# rpi_shield.net
KiCad netlist of a schematic drawn in EAGLE
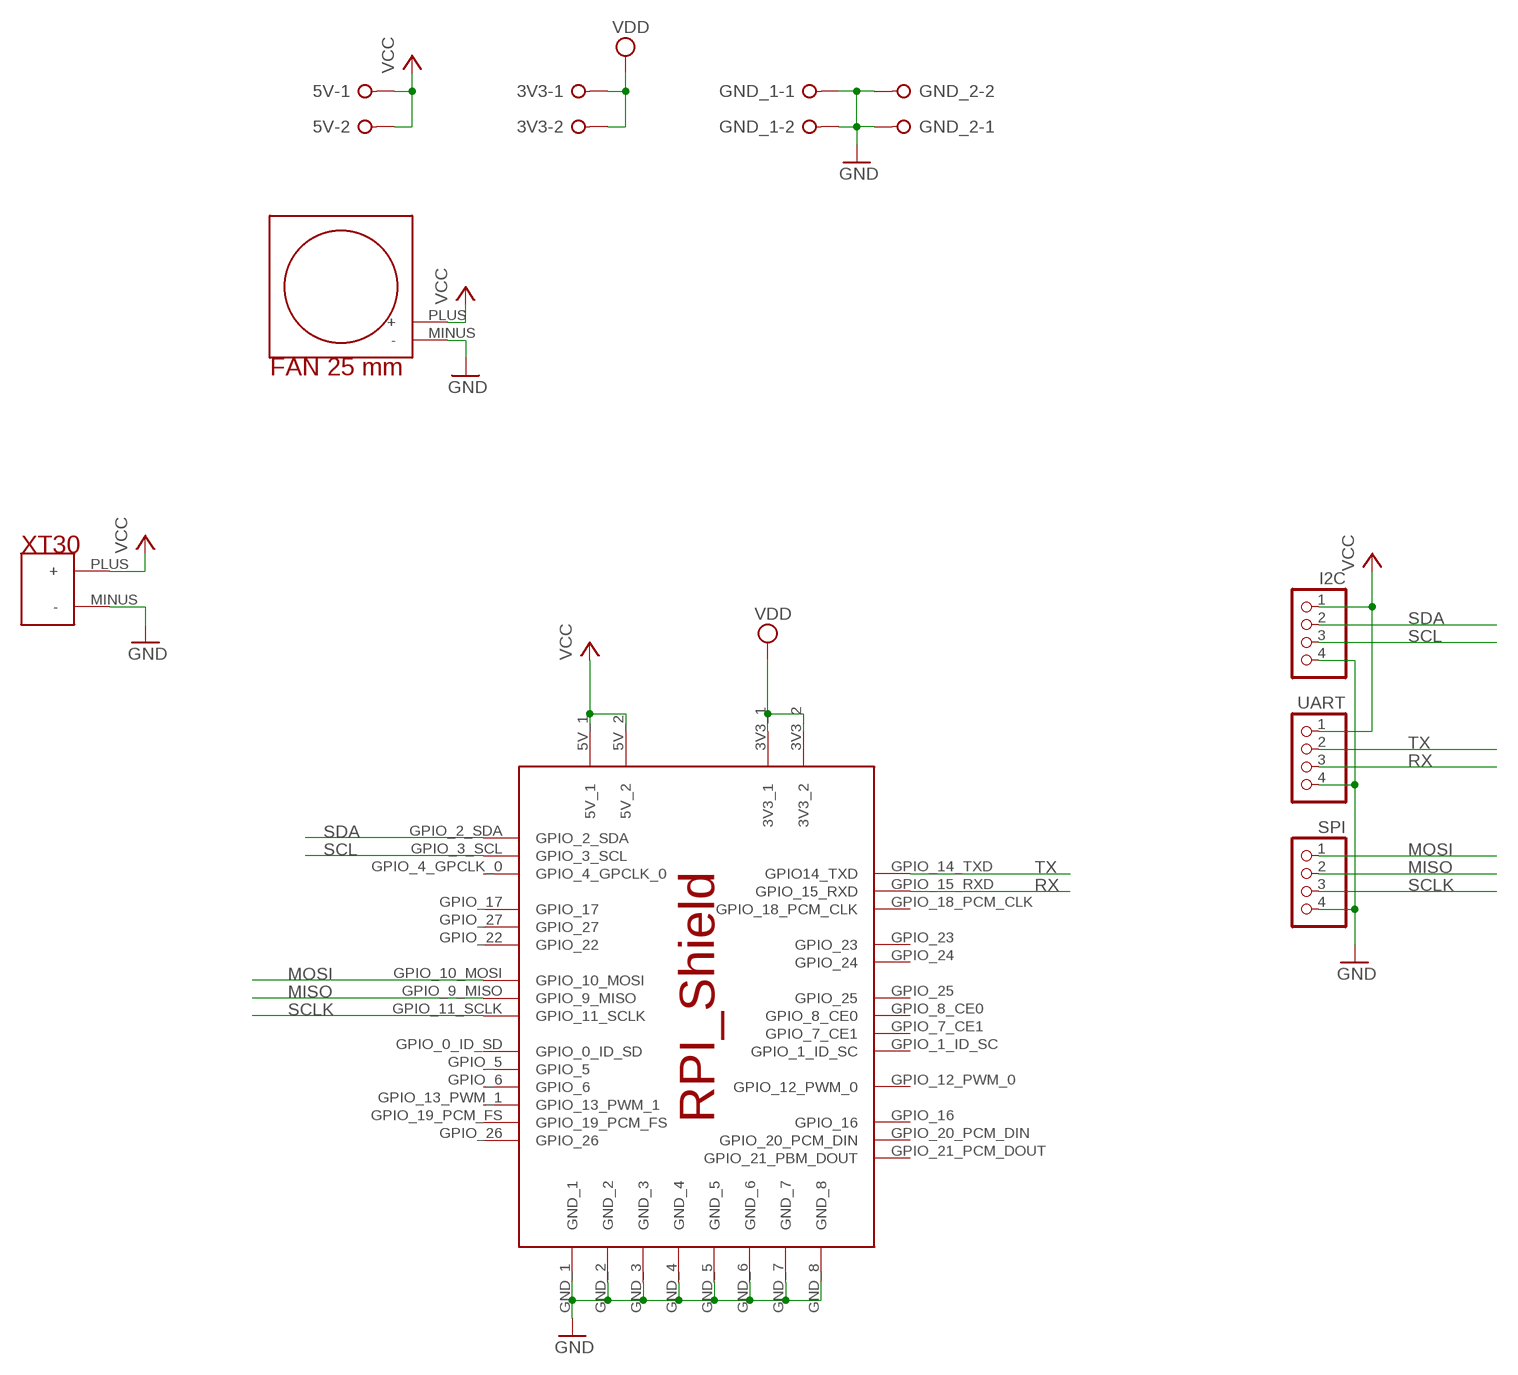
[diagram p0: schematic, sheet 1]

(export (version "E")
  (design (tool "Eeschema 10.0.6"))
  (components
    (comp (ref "3V3")
      (value "W237-02P")
      (footprint "eagle-import:W237-132")
      (libsource (lib "eagle-import") (part "W237-02P"))
    )
    (comp (ref "5V")
      (value "W237-02P")
      (footprint "eagle-import:W237-132")
      (libsource (lib "eagle-import") (part "W237-02P"))
    )
    (comp (ref "GND_1")
      (value "W237-02P")
      (footprint "eagle-import:W237-132")
      (libsource (lib "eagle-import") (part "W237-02P"))
    )
    (comp (ref "GND_2")
      (value "W237-02P")
      (footprint "eagle-import:W237-132")
      (libsource (lib "eagle-import") (part "W237-02P"))
    )
    (comp (ref "I2C")
      (value "PINHD-1X4/90")
      (footprint "eagle-import:1X04_90")
      (libsource (lib "eagle-import") (part "PINHD-1X4/90"))
    )
    (comp (ref "SPI")
      (value "PINHD-1X4/90")
      (footprint "eagle-import:1X04_90")
      (libsource (lib "eagle-import") (part "PINHD-1X4/90"))
    )
    (comp (ref "U$1")
      (value "RPI_SHIELD")
      (footprint "eagle-import:RPI_SHIELD")
      (libsource (lib "eagle-import") (part "RPI_SHIELD"))
    )
    (comp (ref "U$2")
      (value "XT30_90DEG")
      (footprint "eagle-import:XT30_90DEG_FOOTPRINT")
      (libsource (lib "eagle-import") (part "XT30_90DEG"))
    )
    (comp (ref "U$3")
      (value "FAN_25_MM")
      (footprint "eagle-import:FAN_25_MM")
      (libsource (lib "eagle-import") (part "FAN_25_MM"))
    )
    (comp (ref "UART")
      (value "PINHD-1X4/90")
      (footprint "eagle-import:1X04_90")
      (libsource (lib "eagle-import") (part "PINHD-1X4/90"))
    )
  )
  (nets
    (net (code "1") (name "/MISO") (class "Default")
      (node (ref "SPI") (pin "2") (pinfunction "2_2") (pintype "passive"))
      (node (ref "U$1") (pin "GPIO_9_MISO") (pinfunction "GPIO_9_MISO_GPIO_9_MISO") (pintype "bidirectional"))
    )
    (net (code "2") (name "/MOSI") (class "Default")
      (node (ref "SPI") (pin "1") (pinfunction "1_1") (pintype "passive"))
      (node (ref "U$1") (pin "GPIO_10_MOSI") (pinfunction "GPIO_10_MOSI_GPIO_10_MOSI") (pintype "bidirectional"))
    )
    (net (code "3") (name "/RX") (class "Default")
      (node (ref "U$1") (pin "GPIO_15_RXD") (pinfunction "GPIO_15_RXD_GPIO_15_RXD") (pintype "bidirectional"))
      (node (ref "UART") (pin "3") (pinfunction "3_3") (pintype "passive"))
    )
    (net (code "4") (name "/SCL") (class "Default")
      (node (ref "I2C") (pin "3") (pinfunction "3_3") (pintype "passive"))
      (node (ref "U$1") (pin "GPIO_3_SCL") (pinfunction "GPIO_3_SCL_GPIO_3_SCL") (pintype "bidirectional"))
    )
    (net (code "5") (name "/SCLK") (class "Default")
      (node (ref "SPI") (pin "3") (pinfunction "3_3") (pintype "passive"))
      (node (ref "U$1") (pin "GPIO_11_SCLK") (pinfunction "GPIO_11_SCLK_GPIO_11_SCLK") (pintype "bidirectional"))
    )
    (net (code "6") (name "/SDA") (class "Default")
      (node (ref "I2C") (pin "2") (pinfunction "2_2") (pintype "passive"))
      (node (ref "U$1") (pin "GPIO_2_SDA") (pinfunction "GPIO_2_SDA_GPIO_2_SDA") (pintype "bidirectional"))
    )
    (net (code "7") (name "/TX") (class "Default")
      (node (ref "U$1") (pin "GPIO_14_TXD") (pinfunction "GPIO14_TXD_GPIO_14_TXD") (pintype "bidirectional"))
      (node (ref "UART") (pin "2") (pinfunction "2_2") (pintype "passive"))
    )
    (net (code "8") (name "GND") (class "Default")
      (node (ref "GND_1") (pin "1") (pinfunction "KL_1") (pintype "passive"))
      (node (ref "GND_1") (pin "2") (pinfunction "KL_2") (pintype "passive"))
      (node (ref "GND_2") (pin "1") (pinfunction "KL_1") (pintype "passive"))
      (node (ref "GND_2") (pin "2") (pinfunction "KL_2") (pintype "passive"))
      (node (ref "I2C") (pin "4") (pinfunction "4_4") (pintype "passive"))
      (node (ref "SPI") (pin "4") (pinfunction "4_4") (pintype "passive"))
      (node (ref "U$1") (pin "GND_1") (pinfunction "GND_1_GND_1") (pintype "bidirectional"))
      (node (ref "U$1") (pin "GND_2") (pinfunction "GND_2_GND_2") (pintype "bidirectional"))
      (node (ref "U$1") (pin "GND_3") (pinfunction "GND_3_GND_3") (pintype "bidirectional"))
      (node (ref "U$1") (pin "GND_4") (pinfunction "GND_4_GND_4") (pintype "bidirectional"))
      (node (ref "U$1") (pin "GND_5") (pinfunction "GND_5_GND_5") (pintype "bidirectional"))
      (node (ref "U$1") (pin "GND_6") (pinfunction "GND_6_GND_6") (pintype "bidirectional"))
      (node (ref "U$1") (pin "GND_7") (pinfunction "GND_7_GND_7") (pintype "bidirectional"))
      (node (ref "U$1") (pin "GND_8") (pinfunction "GND_8_GND_8") (pintype "bidirectional"))
      (node (ref "U$2") (pin "MINUS") (pinfunction "-_MINUS") (pintype "bidirectional"))
      (node (ref "U$3") (pin "MINUS") (pinfunction "-_MINUS") (pintype "bidirectional"))
      (node (ref "UART") (pin "4") (pinfunction "4_4") (pintype "passive"))
    )
    (net (code "9") (name "VCC") (class "Default")
      (node (ref "5V") (pin "1") (pinfunction "KL_1") (pintype "passive"))
      (node (ref "5V") (pin "2") (pinfunction "KL_2") (pintype "passive"))
      (node (ref "I2C") (pin "1") (pinfunction "1_1") (pintype "passive"))
      (node (ref "U$1") (pin "5V_1") (pinfunction "5V_1_5V_1") (pintype "bidirectional"))
      (node (ref "U$1") (pin "5V_2") (pinfunction "5V_2_5V_2") (pintype "bidirectional"))
      (node (ref "U$2") (pin "PLUS") (pinfunction "+_PLUS") (pintype "bidirectional"))
      (node (ref "U$3") (pin "PLUS") (pinfunction "+_PLUS") (pintype "bidirectional"))
      (node (ref "UART") (pin "1") (pinfunction "1_1") (pintype "passive"))
    )
    (net (code "10") (name "VDD") (class "Default")
      (node (ref "3V3") (pin "1") (pinfunction "KL_1") (pintype "passive"))
      (node (ref "3V3") (pin "2") (pinfunction "KL_2") (pintype "passive"))
      (node (ref "U$1") (pin "3V3_1") (pinfunction "3V3_1_3V3_1") (pintype "bidirectional"))
      (node (ref "U$1") (pin "3V3_2") (pinfunction "3V3_2_3V3_2") (pintype "bidirectional"))
    )
    (net (code "11") (name "unconnected-(U$1-GPIO_21_PBM_DOUT-PadGPIO_21_PCM_DOUT)") (class "Default")
      (node (ref "U$1") (pin "GPIO_21_PCM_DOUT") (pinfunction "GPIO_21_PBM_DOUT_GPIO_21_PCM_DOUT") (pintype "bidirectional"))
    )
    (net (code "12") (name "unconnected-(U$1-PadGPIO_0_ID_SD)") (class "Default")
      (node (ref "U$1") (pin "GPIO_0_ID_SD") (pinfunction "GPIO_0_ID_SD_GPIO_0_ID_SD") (pintype "bidirectional"))
    )
    (net (code "13") (name "unconnected-(U$1-PadGPIO_1_ID_SC)") (class "Default")
      (node (ref "U$1") (pin "GPIO_1_ID_SC") (pinfunction "GPIO_1_ID_SC_GPIO_1_ID_SC") (pintype "bidirectional"))
    )
    (net (code "14") (name "unconnected-(U$1-PadGPIO_4_GPCLK_0)") (class "Default")
      (node (ref "U$1") (pin "GPIO_4_GPCLK_0") (pinfunction "GPIO_4_GPCLK_0_GPIO_4_GPCLK_0") (pintype "bidirectional"))
    )
    (net (code "15") (name "unconnected-(U$1-PadGPIO_5)") (class "Default")
      (node (ref "U$1") (pin "GPIO_5") (pinfunction "GPIO_5_GPIO_5") (pintype "bidirectional"))
    )
    (net (code "16") (name "unconnected-(U$1-PadGPIO_6)") (class "Default")
      (node (ref "U$1") (pin "GPIO_6") (pinfunction "GPIO_6_GPIO_6") (pintype "bidirectional"))
    )
    (net (code "17") (name "unconnected-(U$1-PadGPIO_7_CE1)") (class "Default")
      (node (ref "U$1") (pin "GPIO_7_CE1") (pinfunction "GPIO_7_CE1_GPIO_7_CE1") (pintype "bidirectional"))
    )
    (net (code "18") (name "unconnected-(U$1-PadGPIO_8_CE0)") (class "Default")
      (node (ref "U$1") (pin "GPIO_8_CE0") (pinfunction "GPIO_8_CE0_GPIO_8_CE0") (pintype "bidirectional"))
    )
    (net (code "19") (name "unconnected-(U$1-PadGPIO_12_PWM_0)") (class "Default")
      (node (ref "U$1") (pin "GPIO_12_PWM_0") (pinfunction "GPIO_12_PWM_0_GPIO_12_PWM_0") (pintype "bidirectional"))
    )
    (net (code "20") (name "unconnected-(U$1-PadGPIO_13_PWM_1)") (class "Default")
      (node (ref "U$1") (pin "GPIO_13_PWM_1") (pinfunction "GPIO_13_PWM_1_GPIO_13_PWM_1") (pintype "bidirectional"))
    )
    (net (code "21") (name "unconnected-(U$1-PadGPIO_16)") (class "Default")
      (node (ref "U$1") (pin "GPIO_16") (pinfunction "GPIO_16_GPIO_16") (pintype "bidirectional"))
    )
    (net (code "22") (name "unconnected-(U$1-PadGPIO_17)") (class "Default")
      (node (ref "U$1") (pin "GPIO_17") (pinfunction "GPIO_17_GPIO_17") (pintype "bidirectional"))
    )
    (net (code "23") (name "unconnected-(U$1-PadGPIO_18_PCM_CLK)") (class "Default")
      (node (ref "U$1") (pin "GPIO_18_PCM_CLK") (pinfunction "GPIO_18_PCM_CLK_GPIO_18_PCM_CLK") (pintype "bidirectional"))
    )
    (net (code "24") (name "unconnected-(U$1-PadGPIO_19_PCM_FS)") (class "Default")
      (node (ref "U$1") (pin "GPIO_19_PCM_FS") (pinfunction "GPIO_19_PCM_FS_GPIO_19_PCM_FS") (pintype "bidirectional"))
    )
    (net (code "25") (name "unconnected-(U$1-PadGPIO_20_PCM_DIN)") (class "Default")
      (node (ref "U$1") (pin "GPIO_20_PCM_DIN") (pinfunction "GPIO_20_PCM_DIN_GPIO_20_PCM_DIN") (pintype "bidirectional"))
    )
    (net (code "26") (name "unconnected-(U$1-PadGPIO_22)") (class "Default")
      (node (ref "U$1") (pin "GPIO_22") (pinfunction "GPIO_22_GPIO_22") (pintype "bidirectional"))
    )
    (net (code "27") (name "unconnected-(U$1-PadGPIO_23)") (class "Default")
      (node (ref "U$1") (pin "GPIO_23") (pinfunction "GPIO_23_GPIO_23") (pintype "bidirectional"))
    )
    (net (code "28") (name "unconnected-(U$1-PadGPIO_24)") (class "Default")
      (node (ref "U$1") (pin "GPIO_24") (pinfunction "GPIO_24_GPIO_24") (pintype "bidirectional"))
    )
    (net (code "29") (name "unconnected-(U$1-PadGPIO_25)") (class "Default")
      (node (ref "U$1") (pin "GPIO_25") (pinfunction "GPIO_25_GPIO_25") (pintype "bidirectional"))
    )
    (net (code "30") (name "unconnected-(U$1-PadGPIO_26)") (class "Default")
      (node (ref "U$1") (pin "GPIO_26") (pinfunction "GPIO_26_GPIO_26") (pintype "bidirectional"))
    )
    (net (code "31") (name "unconnected-(U$1-PadGPIO_27)") (class "Default")
      (node (ref "U$1") (pin "GPIO_27") (pinfunction "GPIO_27_GPIO_27") (pintype "bidirectional"))
    )
  )
)
